# Connectors.net
KiCad netlist of a schematic drawn in Altium Designer
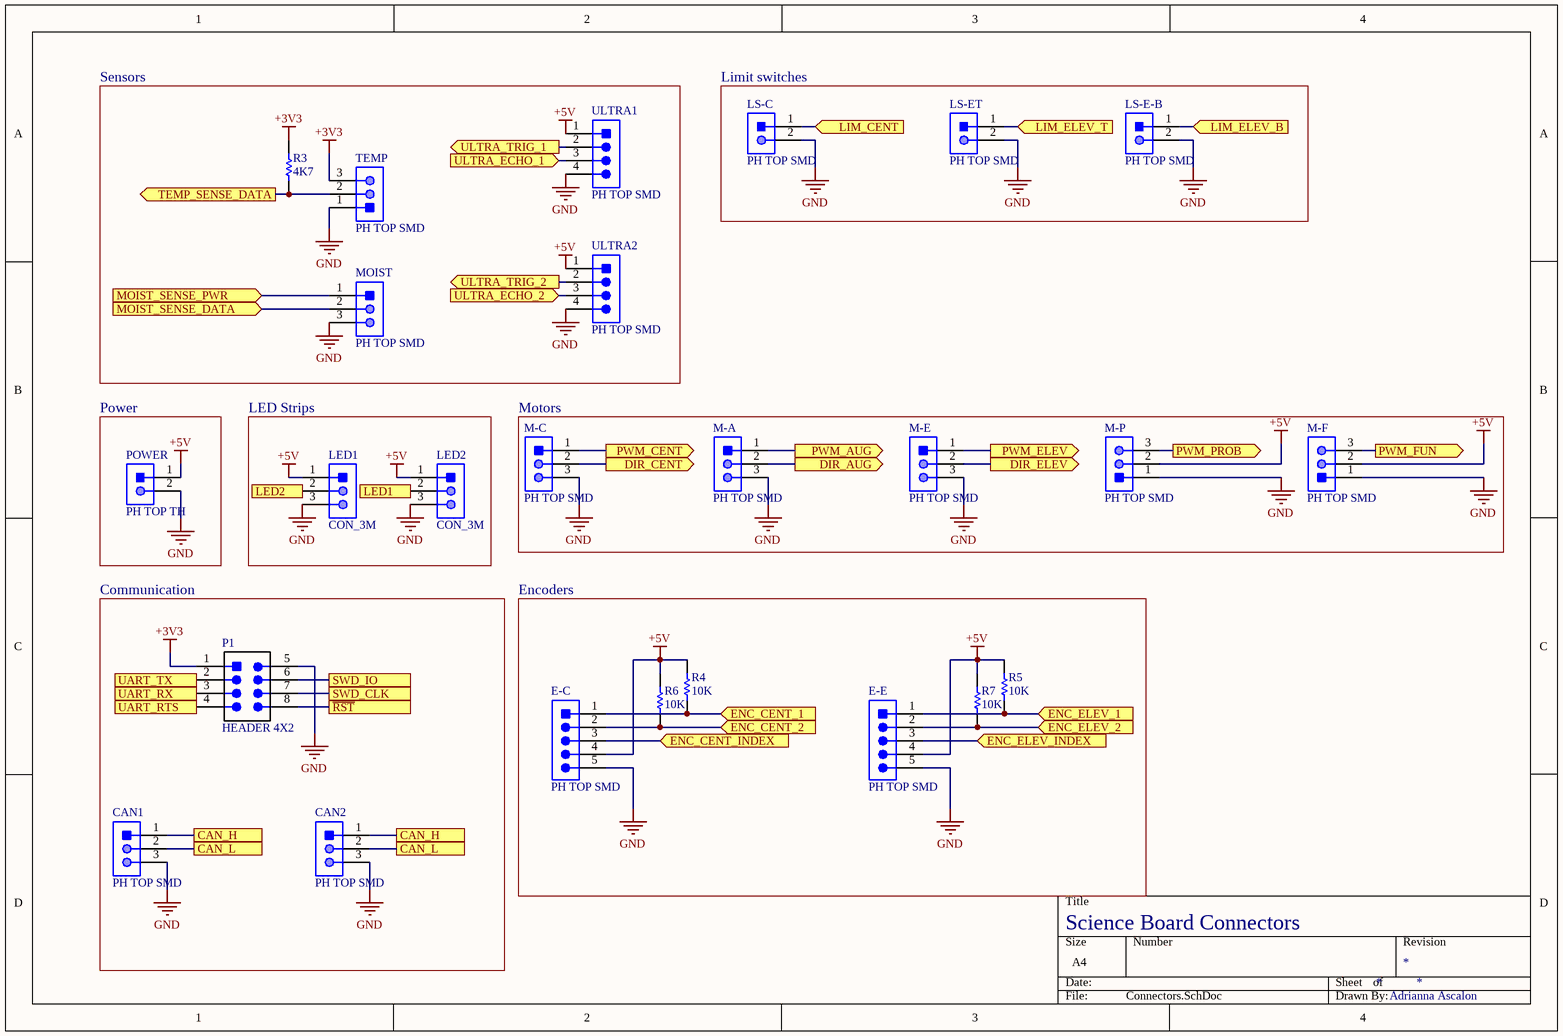
[diagram p0: Connectors.SchDoc]

(export (version "E")
  (design (tool "Eeschema 10.0.6"))
  (components
    (comp (ref "CAN1")
      (value "PH TOP SMD")
      (footprint "JST-B3B-SM4-TB")
      (description "CONN HEADER PH TOP 3POS 2MM SMD")
      (fields (field (name "MANUFACTURER") "JST") (field (name "PART NUMBER") "B3B-PH-SM4-TB"))
      (libsource (lib "UWRT_Schematic_Library_2019") (part "CON_3M_PH_TOP_SMT"))
    )
    (comp (ref "CAN2")
      (value "PH TOP SMD")
      (footprint "JST-B3B-SM4-TB")
      (description "CONN HEADER PH TOP 3POS 2MM SMD")
      (fields (field (name "MANUFACTURER") "JST") (field (name "PART NUMBER") "B3B-PH-SM4-TB"))
      (libsource (lib "UWRT_Schematic_Library_2019") (part "CON_3M_PH_TOP_SMT"))
    )
    (comp (ref "E-C")
      (value "PH TOP SMD")
      (footprint "JST-B5B-SM4-TB")
      (description "CONN HEADER PH TOP 5POS 2MM SMD")
      (fields (field (name "MANUFACTURER") "JST") (field (name "PART NUMBER") "B5B-PH-SM4-TB"))
      (libsource (lib "UWRT_Schematic_Library_2019") (part "CON_5M_PH_TOP_SMT"))
    )
    (comp (ref "E-E")
      (value "PH TOP SMD")
      (footprint "JST-B5B-SM4-TB")
      (description "CONN HEADER PH TOP 5POS 2MM SMD")
      (fields (field (name "MANUFACTURER") "JST") (field (name "PART NUMBER") "B5B-PH-SM4-TB"))
      (libsource (lib "UWRT_Schematic_Library_2019") (part "CON_5M_PH_TOP_SMT"))
    )
    (comp (ref "LED1")
      (value "CON_3M")
      (footprint "JST-B3B-SM4-TB")
      (libsource (lib "UWRT_Schematic_Library_2019") (part "CON_3M"))
    )
    (comp (ref "LED2")
      (value "CON_3M")
      (footprint "JST-B3B-SM4-TB")
      (libsource (lib "UWRT_Schematic_Library_2019") (part "CON_3M"))
    )
    (comp (ref "LS-C")
      (value "PH TOP SMD")
      (footprint "JST-B2B-SM4-TB")
      (description "CONN HEADER PH TOP 2POS 2MM SMD")
      (fields (field (name "MANUFACTURER") "JST") (field (name "PART NUMBER") "B2B-PH-SM4-TB"))
      (libsource (lib "UWRT_Schematic_Library_2019") (part "CON_2M_PH_TOP_SMT"))
    )
    (comp (ref "LS-E-B")
      (value "PH TOP SMD")
      (footprint "JST-B2B-SM4-TB")
      (description "CONN HEADER PH TOP 2POS 2MM SMD")
      (fields (field (name "MANUFACTURER") "JST") (field (name "PART NUMBER") "B2B-PH-SM4-TB"))
      (libsource (lib "UWRT_Schematic_Library_2019") (part "CON_2M_PH_TOP_SMT"))
    )
    (comp (ref "LS-ET")
      (value "PH TOP SMD")
      (footprint "JST-B2B-SM4-TB")
      (description "CONN HEADER PH TOP 2POS 2MM SMD")
      (fields (field (name "MANUFACTURER") "JST") (field (name "PART NUMBER") "B2B-PH-SM4-TB"))
      (libsource (lib "UWRT_Schematic_Library_2019") (part "CON_2M_PH_TOP_SMT"))
    )
    (comp (ref "M-A")
      (value "PH TOP SMD")
      (footprint "JST-B3B-SM4-TB")
      (description "CONN HEADER PH TOP 3POS 2MM SMD")
      (fields (field (name "MANUFACTURER") "JST") (field (name "PART NUMBER") "B3B-PH-SM4-TB"))
      (libsource (lib "UWRT_Schematic_Library_2019") (part "CON_3M_PH_TOP_SMT"))
    )
    (comp (ref "M-C")
      (value "PH TOP SMD")
      (footprint "JST-B3B-SM4-TB")
      (description "CONN HEADER PH TOP 3POS 2MM SMD")
      (fields (field (name "MANUFACTURER") "JST") (field (name "PART NUMBER") "B3B-PH-SM4-TB"))
      (libsource (lib "UWRT_Schematic_Library_2019") (part "CON_3M_PH_TOP_SMT"))
    )
    (comp (ref "M-E")
      (value "PH TOP SMD")
      (footprint "JST-B3B-SM4-TB")
      (description "CONN HEADER PH TOP 3POS 2MM SMD")
      (fields (field (name "MANUFACTURER") "JST") (field (name "PART NUMBER") "B3B-PH-SM4-TB"))
      (libsource (lib "UWRT_Schematic_Library_2019") (part "CON_3M_PH_TOP_SMT"))
    )
    (comp (ref "M-F")
      (value "PH TOP SMD")
      (footprint "JST-B3B-SM4-TB")
      (description "CONN HEADER PH TOP 3POS 2MM SMD")
      (fields (field (name "MANUFACTURER") "JST") (field (name "PART NUMBER") "B3B-PH-SM4-TB"))
      (libsource (lib "") (part "CON_3M_PH_TOP_SMT_3"))
    )
    (comp (ref "M-P")
      (value "PH TOP SMD")
      (footprint "JST-B3B-SM4-TB")
      (description "CONN HEADER PH TOP 3POS 2MM SMD")
      (fields (field (name "MANUFACTURER") "JST") (field (name "PART NUMBER") "B3B-PH-SM4-TB"))
      (libsource (lib "") (part "CON_3M_PH_TOP_SMT_3"))
    )
    (comp (ref "MOIST")
      (value "PH TOP SMD")
      (footprint "JST-B3B-SM4-TB")
      (description "CONN HEADER PH TOP 3POS 2MM SMD")
      (fields (field (name "MANUFACTURER") "JST") (field (name "PART NUMBER") "B3B-PH-SM4-TB"))
      (libsource (lib "") (part "CON_3M_PH_TOP_SMT_1"))
    )
    (comp (ref "P1")
      (value "HEADER 4X2")
      (footprint "UWRT_Footprint_Library_2019:HEADER_2X4")
      (description "Header, 4-Pin Dual row")
      (fields (field (name "MPN") "GRPB042VWVN-RC") (field (name "DIGIKEY PART NUMBER") "S9015E-04-ND"))
      (libsource (lib "UWRT_Schematic_Library_2019") (part "HEADER 4X2"))
    )
    (comp (ref "POWER")
      (value "PH TOP TH")
      (footprint "JST-B2B-PHSK")
      (description "CONN HEADER PH TOP 2POS 2MM")
      (fields (field (name "MANUFACTURER") "JST") (field (name "PART NUMBER") "B2B-PH-K-S"))
      (libsource (lib "UWRT_Schematic_Library_2019") (part "CON_2M_PH_TOP_TH"))
    )
    (comp (ref "R3")
      (value "4K7")
      (footprint "RESC0603(1608)_N")
      (description "RES SMD 4.7K OHM 5% 1/10W 0603")
      (fields (field (name "MANUFACTURER") "Yageo") (field (name "TOLERANCE") "5%"))
      (libsource (lib "UWRT_Schematic_Library_2019") (part "RES_4K7_0603"))
    )
    (comp (ref "R4")
      (value "10K")
      (footprint "RESC0603(1608)_N")
      (description "RES SMD 10K OHM 5% 1/10W 0603")
      (fields (field (name "MANUFACTURER") "Yageo") (field (name "TOLERANCE") "5%"))
      (libsource (lib "UWRT_Schematic_Library_2019") (part "RES_10K_0603"))
    )
    (comp (ref "R5")
      (value "10K")
      (footprint "RESC0603(1608)_N")
      (description "RES SMD 10K OHM 5% 1/10W 0603")
      (fields (field (name "MANUFACTURER") "Yageo") (field (name "TOLERANCE") "5%"))
      (libsource (lib "UWRT_Schematic_Library_2019") (part "RES_10K_0603"))
    )
    (comp (ref "R6")
      (value "10K")
      (footprint "RESC0603(1608)_N")
      (description "RES SMD 10K OHM 5% 1/10W 0603")
      (fields (field (name "MANUFACTURER") "Yageo") (field (name "TOLERANCE") "5%"))
      (libsource (lib "UWRT_Schematic_Library_2019") (part "RES_10K_0603"))
    )
    (comp (ref "R7")
      (value "10K")
      (footprint "RESC0603(1608)_N")
      (description "RES SMD 10K OHM 5% 1/10W 0603")
      (fields (field (name "MANUFACTURER") "Yageo") (field (name "TOLERANCE") "5%"))
      (libsource (lib "UWRT_Schematic_Library_2019") (part "RES_10K_0603"))
    )
    (comp (ref "TEMP")
      (value "PH TOP SMD")
      (footprint "JST-B3B-SM4-TB")
      (description "CONN HEADER PH TOP 3POS 2MM SMD")
      (fields (field (name "MANUFACTURER") "JST") (field (name "PART NUMBER") "B3B-PH-SM4-TB"))
      (libsource (lib "") (part "CON_3M_PH_TOP_SMT_2"))
    )
    (comp (ref "ULTRA1")
      (value "PH TOP SMD")
      (footprint "JST-B4B-SM4-TB")
      (description "CONN HEADER PH TOP 4POS 2MM SMD")
      (fields (field (name "MANUFACTURER") "JST") (field (name "PART NUMBER") "B4B-PH-SM4-TB"))
      (libsource (lib "UWRT_Schematic_Library_2019") (part "CON_4M_PH_TOP_SMT"))
    )
    (comp (ref "ULTRA2")
      (value "PH TOP SMD")
      (footprint "JST-B4B-SM4-TB")
      (description "CONN HEADER PH TOP 4POS 2MM SMD")
      (fields (field (name "MANUFACTURER") "JST") (field (name "PART NUMBER") "B4B-PH-SM4-TB"))
      (libsource (lib "UWRT_Schematic_Library_2019") (part "CON_4M_PH_TOP_SMT"))
    )
  )
  (nets
    (net (code "1") (name "+3V3") (class "Default")
      (node (ref "P1") (pin "1") (pinfunction "VCC_1") (pintype "passive"))
      (node (ref "R3") (pin "2") (pinfunction "2_2") (pintype "passive"))
      (node (ref "TEMP") (pin "3") (pinfunction "3_3") (pintype "passive"))
    )
    (net (code "2") (name "+5V") (class "Default")
      (node (ref "E-C") (pin "4") (pinfunction "4_4") (pintype "passive"))
      (node (ref "E-E") (pin "4") (pinfunction "4_4") (pintype "passive"))
      (node (ref "LED1") (pin "1") (pinfunction "1_1") (pintype "passive"))
      (node (ref "LED2") (pin "1") (pinfunction "1_1") (pintype "passive"))
      (node (ref "M-F") (pin "2") (pinfunction "2_2") (pintype "passive"))
      (node (ref "M-P") (pin "2") (pinfunction "2_2") (pintype "passive"))
      (node (ref "POWER") (pin "1") (pinfunction "1_1") (pintype "passive"))
      (node (ref "R4") (pin "2") (pinfunction "2_2") (pintype "passive"))
      (node (ref "R5") (pin "2") (pinfunction "2_2") (pintype "passive"))
      (node (ref "R6") (pin "2") (pinfunction "2_2") (pintype "passive"))
      (node (ref "R7") (pin "2") (pinfunction "2_2") (pintype "passive"))
      (node (ref "ULTRA1") (pin "1") (pinfunction "1_1") (pintype "passive"))
      (node (ref "ULTRA2") (pin "1") (pinfunction "1_1") (pintype "passive"))
    )
    (net (code "3") (name "/CAN_H") (class "Default")
      (node (ref "CAN1") (pin "1") (pinfunction "1_1") (pintype "passive"))
      (node (ref "CAN2") (pin "1") (pinfunction "1_1") (pintype "passive"))
    )
    (net (code "4") (name "/CAN_L") (class "Default")
      (node (ref "CAN1") (pin "2") (pinfunction "2_2") (pintype "passive"))
      (node (ref "CAN2") (pin "2") (pinfunction "2_2") (pintype "passive"))
    )
    (net (code "5") (name "/DIR_AUG") (class "Default")
      (node (ref "M-A") (pin "2") (pinfunction "2_2") (pintype "passive"))
    )
    (net (code "6") (name "/DIR_CENT") (class "Default")
      (node (ref "M-C") (pin "2") (pinfunction "2_2") (pintype "passive"))
    )
    (net (code "7") (name "/DIR_ELEV") (class "Default")
      (node (ref "M-E") (pin "2") (pinfunction "2_2") (pintype "passive"))
    )
    (net (code "8") (name "/ENC_CENT_1") (class "Default")
      (node (ref "E-C") (pin "1") (pinfunction "1_1") (pintype "passive"))
      (node (ref "R4") (pin "1") (pinfunction "1_1") (pintype "passive"))
    )
    (net (code "9") (name "/ENC_CENT_2") (class "Default")
      (node (ref "E-C") (pin "2") (pinfunction "2_2") (pintype "passive"))
      (node (ref "R6") (pin "1") (pinfunction "1_1") (pintype "passive"))
    )
    (net (code "10") (name "/ENC_CENT_INDEX") (class "Default")
      (node (ref "E-C") (pin "3") (pinfunction "3_3") (pintype "passive"))
    )
    (net (code "11") (name "/ENC_ELEV_1") (class "Default")
      (node (ref "E-E") (pin "1") (pinfunction "1_1") (pintype "passive"))
      (node (ref "R5") (pin "1") (pinfunction "1_1") (pintype "passive"))
    )
    (net (code "12") (name "/ENC_ELEV_2") (class "Default")
      (node (ref "E-E") (pin "2") (pinfunction "2_2") (pintype "passive"))
      (node (ref "R7") (pin "1") (pinfunction "1_1") (pintype "passive"))
    )
    (net (code "13") (name "/ENC_ELEV_INDEX") (class "Default")
      (node (ref "E-E") (pin "3") (pinfunction "3_3") (pintype "passive"))
    )
    (net (code "14") (name "/LED1") (class "Default")
      (node (ref "LED2") (pin "2") (pinfunction "2_2") (pintype "passive"))
    )
    (net (code "15") (name "/LED2") (class "Default")
      (node (ref "LED1") (pin "2") (pinfunction "2_2") (pintype "passive"))
    )
    (net (code "16") (name "/LIM_CENT") (class "Default")
      (node (ref "LS-C") (pin "1") (pinfunction "1_1") (pintype "passive"))
    )
    (net (code "17") (name "/LIM_ELEV_B") (class "Default")
      (node (ref "LS-E-B") (pin "1") (pinfunction "1_1") (pintype "passive"))
    )
    (net (code "18") (name "/LIM_ELEV_T") (class "Default")
      (node (ref "LS-ET") (pin "1") (pinfunction "1_1") (pintype "passive"))
    )
    (net (code "19") (name "/MOIST_SENSE_DATA") (class "Default")
      (node (ref "MOIST") (pin "2") (pinfunction "2_2") (pintype "passive"))
    )
    (net (code "20") (name "/MOIST_SENSE_PWR") (class "Default")
      (node (ref "MOIST") (pin "1") (pinfunction "1_1") (pintype "passive"))
    )
    (net (code "21") (name "/PWM_AUG") (class "Default")
      (node (ref "M-A") (pin "1") (pinfunction "1_1") (pintype "passive"))
    )
    (net (code "22") (name "/PWM_CENT") (class "Default")
      (node (ref "M-C") (pin "1") (pinfunction "1_1") (pintype "passive"))
    )
    (net (code "23") (name "/PWM_ELEV") (class "Default")
      (node (ref "M-E") (pin "1") (pinfunction "1_1") (pintype "passive"))
    )
    (net (code "24") (name "/PWM_FUN") (class "Default")
      (node (ref "M-F") (pin "3") (pinfunction "3_3") (pintype "passive"))
    )
    (net (code "25") (name "/PWM_PROB") (class "Default")
      (node (ref "M-P") (pin "3") (pinfunction "3_3") (pintype "passive"))
    )
    (net (code "26") (name "/SWD_CLK") (class "Default")
      (node (ref "P1") (pin "7") (pinfunction "3_7") (pintype "passive"))
    )
    (net (code "27") (name "/SWD_IO") (class "Default")
      (node (ref "P1") (pin "6") (pinfunction "2_6") (pintype "passive"))
    )
    (net (code "28") (name "/TEMP_SENSE_DATA") (class "Default")
      (node (ref "R3") (pin "1") (pinfunction "1_1") (pintype "passive"))
      (node (ref "TEMP") (pin "2") (pinfunction "2_2") (pintype "passive"))
    )
    (net (code "29") (name "/UART_RTS") (class "Default")
      (node (ref "P1") (pin "4") (pinfunction "4_4") (pintype "passive"))
    )
    (net (code "30") (name "/UART_RX") (class "Default")
      (node (ref "P1") (pin "3") (pinfunction "3_3") (pintype "passive"))
    )
    (net (code "31") (name "/UART_TX") (class "Default")
      (node (ref "P1") (pin "2") (pinfunction "2_2") (pintype "passive"))
    )
    (net (code "32") (name "/ULTRA_ECHO_1") (class "Default")
      (node (ref "ULTRA1") (pin "3") (pinfunction "3_3") (pintype "passive"))
    )
    (net (code "33") (name "/ULTRA_ECHO_2") (class "Default")
      (node (ref "ULTRA2") (pin "3") (pinfunction "3_3") (pintype "passive"))
    )
    (net (code "34") (name "/ULTRA_TRIG_1") (class "Default")
      (node (ref "ULTRA1") (pin "2") (pinfunction "2_2") (pintype "passive"))
    )
    (net (code "35") (name "/ULTRA_TRIG_2") (class "Default")
      (node (ref "ULTRA2") (pin "2") (pinfunction "2_2") (pintype "passive"))
    )
    (net (code "36") (name "/~{RST}") (class "Default")
      (node (ref "P1") (pin "8") (pinfunction "4_8") (pintype "passive"))
    )
    (net (code "37") (name "GND") (class "Default")
      (node (ref "CAN1") (pin "3") (pinfunction "3_3") (pintype "passive"))
      (node (ref "CAN2") (pin "3") (pinfunction "3_3") (pintype "passive"))
      (node (ref "E-C") (pin "5") (pinfunction "5_5") (pintype "passive"))
      (node (ref "E-E") (pin "5") (pinfunction "5_5") (pintype "passive"))
      (node (ref "LED1") (pin "3") (pinfunction "3_3") (pintype "passive"))
      (node (ref "LED2") (pin "3") (pinfunction "3_3") (pintype "passive"))
      (node (ref "LS-C") (pin "2") (pinfunction "2_2") (pintype "passive"))
      (node (ref "LS-E-B") (pin "2") (pinfunction "2_2") (pintype "passive"))
      (node (ref "LS-ET") (pin "2") (pinfunction "2_2") (pintype "passive"))
      (node (ref "M-A") (pin "3") (pinfunction "3_3") (pintype "passive"))
      (node (ref "M-C") (pin "3") (pinfunction "3_3") (pintype "passive"))
      (node (ref "M-E") (pin "3") (pinfunction "3_3") (pintype "passive"))
      (node (ref "M-F") (pin "1") (pinfunction "1_1") (pintype "passive"))
      (node (ref "M-P") (pin "1") (pinfunction "1_1") (pintype "passive"))
      (node (ref "MOIST") (pin "3") (pinfunction "3_3") (pintype "passive"))
      (node (ref "P1") (pin "5") (pinfunction "GND_5") (pintype "passive"))
      (node (ref "POWER") (pin "2") (pinfunction "2_2") (pintype "passive"))
      (node (ref "TEMP") (pin "1") (pinfunction "1_1") (pintype "passive"))
      (node (ref "ULTRA1") (pin "4") (pinfunction "4_4") (pintype "passive"))
      (node (ref "ULTRA2") (pin "4") (pinfunction "4_4") (pintype "passive"))
    )
  )
)
